# Sheet1.net
KiCad netlist of a schematic drawn in Altium Designer
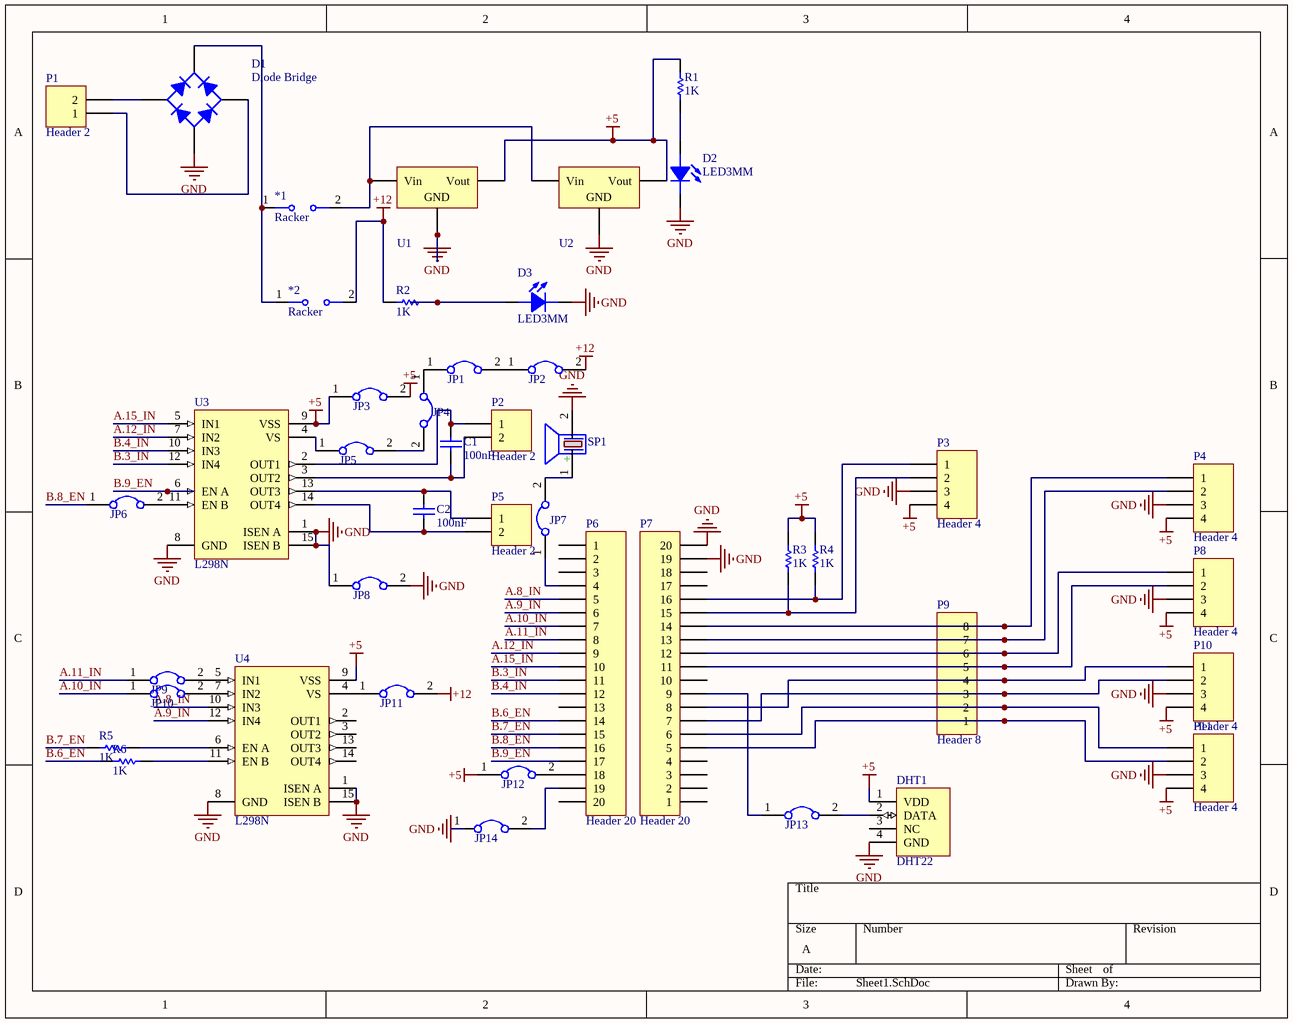
[diagram p0: Sheet1.SchDoc]

(export (version "E")
  (design (tool "Eeschema 10.0.6"))
  (components
    (comp (ref "*1") (value "Racker") (footprint "Racker 2 Pin") (libsource (lib "Switch") (part "Racker")))
    (comp (ref "*2") (value "Racker") (footprint "Racker 2 Pin") (libsource (lib "Switch") (part "Racker")))
    (comp (ref "C1")
      (value "100nF")
      (footprint "Cap-100nF")
      (description "CAP Ceramic Total")
      (fields (field (name "DESIGNER") "Ali Hafizi"))
      (libsource (lib "Altium") (part "CAP CERAMIC TOTAL SIZE"))
    )
    (comp (ref "C2")
      (value "100nF")
      (footprint "Cap-100nF")
      (description "CAP Ceramic Total")
      (fields (field (name "DESIGNER") "Ali Hafizi"))
      (libsource (lib "Altium") (part "CAP CERAMIC TOTAL SIZE"))
    )
    (comp (ref "D1")
      (value "Diode Bridge")
      (footprint "Bridge KBL PACKAGE")
      (description "Full Wave Diode Bridge")
      (fields (field (name "DESIGNER") "Abbas Basereh"))
      (libsource (lib "Altium") (part "Diode Bridge TOTAL SIZE"))
    )
    (comp (ref "D2")
      (value "LED3MM")
      (footprint "LED3mm_GRN")
      (description "Light Emitting Diode")
      (fields (field (name "DESIGNER") "Ali Hafizi"))
      (libsource (lib "Altium") (part "LED 3MM"))
    )
    (comp (ref "D3")
      (value "LED3MM")
      (footprint "LED3mm_GRN")
      (description "Light Emitting Diode")
      (fields (field (name "DESIGNER") "Ali Hafizi"))
      (libsource (lib "Altium") (part "LED 3MM"))
    )
    (comp (ref "DHT1")
      (value "DHT22")
      (footprint "DHT22")
      (description "Digital Humidity & Temprature Sensor")
      (libsource (lib "Altium") (part "DHT22"))
    )
    (comp (ref "JP1") (value "Jumper") (footprint "Jumper") (libsource (lib "Altium") (part "Jumper")))
    (comp (ref "JP2") (value "Jumper") (footprint "Jumper") (libsource (lib "Altium") (part "Jumper")))
    (comp (ref "JP3") (value "Jumper") (footprint "Jumper") (libsource (lib "Altium") (part "Jumper")))
    (comp (ref "JP4") (value "Jumper") (footprint "Jumper") (libsource (lib "Altium") (part "Jumper")))
    (comp (ref "JP5") (value "Jumper") (footprint "Jumper") (libsource (lib "Altium") (part "Jumper")))
    (comp (ref "JP6") (value "Jumper") (footprint "Jumper") (libsource (lib "Altium") (part "Jumper")))
    (comp (ref "JP7") (value "Jumper") (footprint "Jumper") (libsource (lib "Altium") (part "Jumper")))
    (comp (ref "JP8") (value "Jumper") (footprint "Jumper") (libsource (lib "Altium") (part "Jumper")))
    (comp (ref "JP9") (value "Jumper") (footprint "Jumper") (libsource (lib "Altium") (part "Jumper")))
    (comp (ref "JP10") (value "Jumper") (footprint "Jumper") (libsource (lib "Altium") (part "Jumper")))
    (comp (ref "JP11") (value "Jumper") (footprint "Jumper") (libsource (lib "Altium") (part "Jumper")))
    (comp (ref "JP12") (value "Jumper") (footprint "Jumper") (libsource (lib "Altium") (part "Jumper")))
    (comp (ref "JP13") (value "Jumper") (footprint "Jumper") (libsource (lib "Altium") (part "Jumper")))
    (comp (ref "JP14") (value "Jumper") (footprint "Jumper") (libsource (lib "Altium") (part "Jumper")))
    (comp (ref "P1")
      (value "Header 2")
      (footprint "HDR1X2")
      (description "Header, 2-Pin")
      (fields (field (name "PUBLISHER") "Altium Limited"))
      (libsource (lib "") (part "Header 2_1"))
    )
    (comp (ref "P2")
      (value "Header 2")
      (footprint "HDR1X2")
      (description "Header, 2-Pin")
      (fields (field (name "PUBLISHER") "Altium Limited"))
      (libsource (lib "Altium") (part "Header 2"))
    )
    (comp (ref "P3")
      (value "Header 4")
      (footprint "HDR1X4")
      (description "Header, 4-Pin")
      (fields (field (name "PUBLISHER") "Altium Limited"))
      (libsource (lib "Altium") (part "Header 4"))
    )
    (comp (ref "P4")
      (value "Header 4")
      (footprint "HDR1X4")
      (description "Header, 4-Pin")
      (fields (field (name "PUBLISHER") "Altium Limited"))
      (libsource (lib "Altium") (part "Header 4"))
    )
    (comp (ref "P5")
      (value "Header 2")
      (footprint "HDR1X2")
      (description "Header, 2-Pin")
      (fields (field (name "PUBLISHER") "Altium Limited"))
      (libsource (lib "Altium") (part "Header 2"))
    )
    (comp (ref "P6")
      (value "Header 20")
      (footprint "HDR1X20")
      (description "Header, 20-Pin")
      (fields (field (name "PUBLISHER") "Altium Limited"))
      (libsource (lib "") (part "Header 20_1"))
    )
    (comp (ref "P7")
      (value "Header 20")
      (footprint "HDR1X20")
      (description "Header, 20-Pin")
      (fields (field (name "PUBLISHER") "Altium Limited"))
      (libsource (lib "Altium") (part "Header 20"))
    )
    (comp (ref "P8")
      (value "Header 4")
      (footprint "HDR1X4")
      (description "Header, 4-Pin")
      (fields (field (name "PUBLISHER") "Altium Limited"))
      (libsource (lib "Altium") (part "Header 4"))
    )
    (comp (ref "P9")
      (value "Header 8")
      (footprint "HDR1X8")
      (description "Header, 8-Pin")
      (fields (field (name "PUBLISHER") "Altium Limited"))
      (libsource (lib "Altium") (part "Header 8"))
    )
    (comp (ref "P10")
      (value "Header 4")
      (footprint "HDR1X4")
      (description "Header, 4-Pin")
      (fields (field (name "PUBLISHER") "Altium Limited"))
      (libsource (lib "Altium") (part "Header 4"))
    )
    (comp (ref "P11")
      (value "Header 4")
      (footprint "HDR1X4")
      (description "Header, 4-Pin")
      (fields (field (name "PUBLISHER") "Altium Limited"))
      (libsource (lib "Altium") (part "Header 4"))
    )
    (comp (ref "R1")
      (value "1K")
      (footprint "RES-(1/4)")
      (description "TOTAL DIP RESISTOR PACK")
      (fields (field (name "DESIGNER") "Ali Hafizi"))
      (libsource (lib "Altium") (part "RES DIP PACKAGE"))
    )
    (comp (ref "R2")
      (value "1K")
      (footprint "RES-(1/4)")
      (description "TOTAL DIP RESISTOR PACK")
      (fields (field (name "DESIGNER") "Ali Hafizi"))
      (libsource (lib "Altium") (part "RES DIP PACKAGE"))
    )
    (comp (ref "R3")
      (value "1K")
      (footprint "RES-(1/4)")
      (description "TOTAL DIP RESISTOR PACK")
      (fields (field (name "DESIGNER") "Ali Hafizi"))
      (libsource (lib "Altium") (part "RES DIP PACKAGE"))
    )
    (comp (ref "R4")
      (value "1K")
      (footprint "RES-(1/4)")
      (description "TOTAL DIP RESISTOR PACK")
      (fields (field (name "DESIGNER") "Ali Hafizi"))
      (libsource (lib "Altium") (part "RES DIP PACKAGE"))
    )
    (comp (ref "R5")
      (value "1K")
      (footprint "RES-(1/4)")
      (description "TOTAL DIP RESISTOR PACK")
      (fields (field (name "DESIGNER") "Ali Hafizi"))
      (libsource (lib "Altium") (part "RES DIP PACKAGE"))
    )
    (comp (ref "R6")
      (value "1K")
      (footprint "RES-(1/4)")
      (description "TOTAL DIP RESISTOR PACK")
      (fields (field (name "DESIGNER") "Ali Hafizi"))
      (libsource (lib "Altium") (part "RES DIP PACKAGE"))
    )
    (comp (ref "SP1")
      (value "~")
      (footprint "BUZZER 7.62mm DC")
      (description "PIEZO BUZZER ACTIVE")
      (fields (field (name "DESIGNER") "Abbas Basereh") (field (name "PUBLISHER") "Abbas Basereh"))
      (libsource (lib "Altium") (part "PIEZO BUZZER"))
    )
    (comp (ref "U1")
      (value "L7805CV")
      (footprint "TO-220 AB")
      (description "Linear Voltage Regulator IC Positive FIXED")
      (fields (field (name "MANUFACTURER") "STMicroelectronics") (field (name "DESIGNER") "Abbas Basereh"))
      (libsource (lib "Altium") (part "L7805CV-Linear Voltage Regulator IC Positive 1 Output 5V 1.5A TO-220AB"))
    )
    (comp (ref "U2")
      (value "L7805CV")
      (footprint "TO-220 AB")
      (description "Linear Voltage Regulator IC Positive FIXED")
      (fields (field (name "MANUFACTURER") "STMicroelectronics") (field (name "DESIGNER") "Abbas Basereh"))
      (libsource (lib "Altium") (part "L7805CV-Linear Voltage Regulator IC Positive 1 Output 5V 1.5A TO-220AB"))
    )
    (comp (ref "U3")
      (value "L298N")
      (footprint "Multiwatt15V")
      (description "Dual Full Bridge Driver")
      (fields (field (name "PUBLISHER") "Altium Limited"))
      (libsource (lib "Altium") (part "L298N"))
    )
    (comp (ref "U4")
      (value "L298N")
      (footprint "Multiwatt15V")
      (description "Dual Full Bridge Driver")
      (fields (field (name "PUBLISHER") "Altium Limited"))
      (libsource (lib "Altium") (part "L298N"))
    )
  )
  (nets
    (net (code "1") (name "+5") (class "Default")
      (node (ref "DHT1") (pin "1") (pinfunction "VDD_1") (pintype "power_in"))
      (node (ref "JP12") (pin "1") (pinfunction "1_1") (pintype "passive"))
      (node (ref "JP3") (pin "1") (pinfunction "1_1") (pintype "passive"))
      (node (ref "JP3") (pin "2") (pinfunction "2_2") (pintype "passive"))
      (node (ref "P10") (pin "4") (pinfunction "4_4") (pintype "passive"))
      (node (ref "P11") (pin "4") (pinfunction "4_4") (pintype "passive"))
      (node (ref "P3") (pin "4") (pinfunction "4_4") (pintype "passive"))
      (node (ref "P4") (pin "4") (pinfunction "4_4") (pintype "passive"))
      (node (ref "P8") (pin "4") (pinfunction "4_4") (pintype "passive"))
      (node (ref "R1") (pin "2") (pinfunction "2_2") (pintype "passive"))
      (node (ref "R3") (pin "2") (pinfunction "2_2") (pintype "passive"))
      (node (ref "R4") (pin "2") (pinfunction "2_2") (pintype "passive"))
      (node (ref "U1") (pin "3") (pinfunction "Vout_3") (pintype "passive"))
      (node (ref "U2") (pin "3") (pinfunction "Vout_3") (pintype "passive"))
      (node (ref "U3") (pin "9") (pinfunction "VSS_9") (pintype "power_in"))
      (node (ref "U4") (pin "9") (pinfunction "VSS_9") (pintype "power_in"))
    )
    (net (code "2") (name "+12") (class "Default")
      (node (ref "*2") (pin "2") (pinfunction "2_2") (pintype "passive"))
      (node (ref "JP11") (pin "2") (pinfunction "2_2") (pintype "passive"))
      (node (ref "JP2") (pin "2") (pinfunction "2_2") (pintype "passive"))
      (node (ref "R2") (pin "2") (pinfunction "2_2") (pintype "passive"))
    )
    (net (code "3") (name "/A.8_IN") (class "Default")
      (node (ref "P6") (pin "5") (pinfunction "5_5") (pintype "passive"))
      (node (ref "U4") (pin "10") (pinfunction "IN3_10") (pintype "input"))
    )
    (net (code "4") (name "/A.9_IN") (class "Default")
      (node (ref "P6") (pin "6") (pinfunction "6_6") (pintype "passive"))
      (node (ref "U4") (pin "12") (pinfunction "IN4_12") (pintype "input"))
    )
    (net (code "5") (name "/A.10_IN") (class "Default")
      (node (ref "JP10") (pin "1") (pinfunction "1_1") (pintype "passive"))
      (node (ref "P6") (pin "7") (pinfunction "7_7") (pintype "passive"))
    )
    (net (code "6") (name "/A.11_IN") (class "Default")
      (node (ref "JP9") (pin "1") (pinfunction "1_1") (pintype "passive"))
      (node (ref "P6") (pin "8") (pinfunction "8_8") (pintype "passive"))
    )
    (net (code "7") (name "/A.12_IN") (class "Default")
      (node (ref "P6") (pin "9") (pinfunction "9_9") (pintype "passive"))
      (node (ref "U3") (pin "7") (pinfunction "IN2_7") (pintype "input"))
    )
    (net (code "8") (name "/A.15_IN") (class "Default")
      (node (ref "P6") (pin "10") (pinfunction "10_10") (pintype "passive"))
      (node (ref "U3") (pin "5") (pinfunction "IN1_5") (pintype "input"))
    )
    (net (code "9") (name "/B.3_IN") (class "Default")
      (node (ref "P6") (pin "11") (pinfunction "11_11") (pintype "passive"))
      (node (ref "U3") (pin "12") (pinfunction "IN4_12") (pintype "input"))
    )
    (net (code "10") (name "/B.4_IN") (class "Default")
      (node (ref "P6") (pin "12") (pinfunction "12_12") (pintype "passive"))
      (node (ref "U3") (pin "10") (pinfunction "IN3_10") (pintype "input"))
    )
    (net (code "11") (name "/B.6_EN") (class "Default")
      (node (ref "P6") (pin "14") (pinfunction "14_14") (pintype "passive"))
      (node (ref "R6") (pin "1") (pinfunction "1_1") (pintype "passive"))
    )
    (net (code "12") (name "/B.7_EN") (class "Default")
      (node (ref "P6") (pin "15") (pinfunction "15_15") (pintype "passive"))
      (node (ref "R5") (pin "1") (pinfunction "1_1") (pintype "passive"))
    )
    (net (code "13") (name "/B.8_EN") (class "Default")
      (node (ref "JP6") (pin "1") (pinfunction "1_1") (pintype "passive"))
      (node (ref "P6") (pin "16") (pinfunction "16_16") (pintype "passive"))
    )
    (net (code "14") (name "/B.9_EN") (class "Default")
      (node (ref "P6") (pin "17") (pinfunction "17_17") (pintype "passive"))
      (node (ref "U3") (pin "6") (pinfunction "EN_A_6") (pintype "input"))
    )
    (net (code "15") (name "GND") (class "Default")
      (node (ref "D1") (pin "4") (pinfunction "-_4") (pintype "passive"))
      (node (ref "D2") (pin "2") (pinfunction "CATHODE_2") (pintype "passive"))
      (node (ref "D3") (pin "2") (pinfunction "CATHODE_2") (pintype "passive"))
      (node (ref "DHT1") (pin "4") (pinfunction "GND_4") (pintype "power_in"))
      (node (ref "JP14") (pin "1") (pinfunction "1_1") (pintype "passive"))
      (node (ref "JP8") (pin "1") (pinfunction "1_1") (pintype "passive"))
      (node (ref "JP8") (pin "2") (pinfunction "2_2") (pintype "passive"))
      (node (ref "P10") (pin "3") (pinfunction "3_3") (pintype "passive"))
      (node (ref "P11") (pin "3") (pinfunction "3_3") (pintype "passive"))
      (node (ref "P3") (pin "3") (pinfunction "3_3") (pintype "passive"))
      (node (ref "P4") (pin "3") (pinfunction "3_3") (pintype "passive"))
      (node (ref "P7") (pin "19") (pinfunction "19_19") (pintype "passive"))
      (node (ref "P7") (pin "20") (pinfunction "20_20") (pintype "passive"))
      (node (ref "P8") (pin "3") (pinfunction "3_3") (pintype "passive"))
      (node (ref "SP1") (pin "2") (pinfunction "-_2") (pintype "passive"))
      (node (ref "U1") (pin "2") (pinfunction "GND_2") (pintype "passive"))
      (node (ref "U2") (pin "2") (pinfunction "GND_2") (pintype "passive"))
      (node (ref "U3") (pin "1") (pinfunction "ISEN_A_1") (pintype "passive"))
      (node (ref "U3") (pin "15") (pinfunction "ISEN_B_15") (pintype "passive"))
      (node (ref "U3") (pin "8") (pinfunction "GND_8") (pintype "power_in"))
      (node (ref "U4") (pin "1") (pinfunction "ISEN_A_1") (pintype "passive"))
      (node (ref "U4") (pin "15") (pinfunction "ISEN_B_15") (pintype "passive"))
      (node (ref "U4") (pin "8") (pinfunction "GND_8") (pintype "power_in"))
    )
    (net (code "16") (name "Net-(*1-Button)") (class "Default")
      (node (ref "*1") (pin "1") (pinfunction "Button_1") (pintype "passive"))
      (node (ref "*2") (pin "1") (pinfunction "Button_1") (pintype "passive"))
      (node (ref "D1") (pin "1") (pinfunction "+_1") (pintype "passive"))
    )
    (net (code "17") (name "Net-(D1-AC-Pad2)") (class "Default")
      (node (ref "D1") (pin "2") (pinfunction "AC_2") (pintype "passive"))
      (node (ref "P1") (pin "2") (pinfunction "2_2") (pintype "passive"))
    )
    (net (code "18") (name "Net-(D1-AC-Pad3)") (class "Default")
      (node (ref "D1") (pin "3") (pinfunction "AC_3") (pintype "passive"))
      (node (ref "P1") (pin "1") (pinfunction "1_1") (pintype "passive"))
    )
    (net (code "19") (name "Net-(D2-ANODE)") (class "Default")
      (node (ref "D2") (pin "1") (pinfunction "ANODE_1") (pintype "passive"))
      (node (ref "R1") (pin "1") (pinfunction "1_1") (pintype "passive"))
    )
    (net (code "20") (name "Net-(D3-ANODE)") (class "Default")
      (node (ref "D3") (pin "1") (pinfunction "ANODE_1") (pintype "passive"))
      (node (ref "R2") (pin "1") (pinfunction "1_1") (pintype "passive"))
    )
    (net (code "21") (name "Net-(DHT1-DATA)") (class "Default")
      (node (ref "DHT1") (pin "2") (pinfunction "DATA_2") (pintype "bidirectional"))
      (node (ref "JP13") (pin "2") (pinfunction "2_2") (pintype "passive"))
    )
    (net (code "22") (name "Net-(JP1-Pad1)") (class "Default")
      (node (ref "JP1") (pin "1") (pinfunction "1_1") (pintype "passive"))
      (node (ref "JP4") (pin "1") (pinfunction "1_1") (pintype "passive"))
    )
    (net (code "23") (name "Net-(JP1-Pad2)") (class "Default")
      (node (ref "JP1") (pin "2") (pinfunction "2_2") (pintype "passive"))
      (node (ref "JP2") (pin "1") (pinfunction "1_1") (pintype "passive"))
    )
    (net (code "24") (name "Net-(JP4-Pad2)") (class "Default")
      (node (ref "JP4") (pin "2") (pinfunction "2_2") (pintype "passive"))
      (node (ref "JP5") (pin "2") (pinfunction "2_2") (pintype "passive"))
    )
    (net (code "25") (name "Net-(JP7-Pad1)") (class "Default")
      (node (ref "JP7") (pin "1") (pinfunction "1_1") (pintype "passive"))
      (node (ref "P6") (pin "4") (pinfunction "4_4") (pintype "passive"))
    )
    (net (code "26") (name "Net-(JP12-Pad2)") (class "Default")
      (node (ref "JP12") (pin "2") (pinfunction "2_2") (pintype "passive"))
      (node (ref "P6") (pin "18") (pinfunction "18_18") (pintype "passive"))
    )
    (net (code "27") (name "Net-(JP13-Pad1)") (class "Default")
      (node (ref "JP13") (pin "1") (pinfunction "1_1") (pintype "passive"))
      (node (ref "P7") (pin "9") (pinfunction "9_9") (pintype "passive"))
    )
    (net (code "28") (name "Net-(JP14-Pad2)") (class "Default")
      (node (ref "JP14") (pin "2") (pinfunction "2_2") (pintype "passive"))
      (node (ref "P6") (pin "19") (pinfunction "19_19") (pintype "passive"))
    )
    (net (code "29") (name "Net-(P3-Pad1)") (class "Default")
      (node (ref "P3") (pin "1") (pinfunction "1_1") (pintype "passive"))
      (node (ref "P7") (pin "16") (pinfunction "16_16") (pintype "passive"))
      (node (ref "R4") (pin "1") (pinfunction "1_1") (pintype "passive"))
    )
    (net (code "30") (name "Net-(P3-Pad2)") (class "Default")
      (node (ref "P3") (pin "2") (pinfunction "2_2") (pintype "passive"))
      (node (ref "P7") (pin "15") (pinfunction "15_15") (pintype "passive"))
      (node (ref "R3") (pin "1") (pinfunction "1_1") (pintype "passive"))
    )
    (net (code "31") (name "Net-(P4-Pad1)") (class "Default")
      (node (ref "P4") (pin "1") (pinfunction "1_1") (pintype "passive"))
      (node (ref "P7") (pin "14") (pinfunction "14_14") (pintype "passive"))
      (node (ref "P9") (pin "8") (pinfunction "8_8") (pintype "passive"))
    )
    (net (code "32") (name "Net-(P4-Pad2)") (class "Default")
      (node (ref "P4") (pin "2") (pinfunction "2_2") (pintype "passive"))
      (node (ref "P7") (pin "13") (pinfunction "13_13") (pintype "passive"))
      (node (ref "P9") (pin "7") (pinfunction "7_7") (pintype "passive"))
    )
    (net (code "33") (name "Net-(P7-Pad11)") (class "Default")
      (node (ref "P7") (pin "11") (pinfunction "11_11") (pintype "passive"))
      (node (ref "P8") (pin "2") (pinfunction "2_2") (pintype "passive"))
      (node (ref "P9") (pin "5") (pinfunction "5_5") (pintype "passive"))
    )
    (net (code "34") (name "Net-(P7-Pad12)") (class "Default")
      (node (ref "P7") (pin "12") (pinfunction "12_12") (pintype "passive"))
      (node (ref "P8") (pin "1") (pinfunction "1_1") (pintype "passive"))
      (node (ref "P9") (pin "6") (pinfunction "6_6") (pintype "passive"))
    )
    (net (code "35") (name "Net-(P10-Pad1)") (class "Default")
      (node (ref "P10") (pin "1") (pinfunction "1_1") (pintype "passive"))
      (node (ref "P7") (pin "8") (pinfunction "8_8") (pintype "passive"))
      (node (ref "P9") (pin "4") (pinfunction "4_4") (pintype "passive"))
    )
    (net (code "36") (name "Net-(P10-Pad2)") (class "Default")
      (node (ref "P10") (pin "2") (pinfunction "2_2") (pintype "passive"))
      (node (ref "P7") (pin "7") (pinfunction "7_7") (pintype "passive"))
      (node (ref "P9") (pin "3") (pinfunction "3_3") (pintype "passive"))
    )
    (net (code "37") (name "Net-(P11-Pad1)") (class "Default")
      (node (ref "P11") (pin "1") (pinfunction "1_1") (pintype "passive"))
      (node (ref "P7") (pin "6") (pinfunction "6_6") (pintype "passive"))
      (node (ref "P9") (pin "2") (pinfunction "2_2") (pintype "passive"))
    )
    (net (code "38") (name "Net-(P11-Pad2)") (class "Default")
      (node (ref "P11") (pin "2") (pinfunction "2_2") (pintype "passive"))
      (node (ref "P7") (pin "5") (pinfunction "5_5") (pintype "passive"))
      (node (ref "P9") (pin "1") (pinfunction "1_1") (pintype "passive"))
    )
    (net (code "39") (name "Net-(SP1-+)") (class "Default")
      (node (ref "JP7") (pin "2") (pinfunction "2_2") (pintype "passive"))
      (node (ref "SP1") (pin "1") (pinfunction "+_1") (pintype "passive"))
    )
    (net (code "40") (name "Net-(U1-Vin)") (class "Default")
      (node (ref "*1") (pin "2") (pinfunction "2_2") (pintype "passive"))
      (node (ref "U1") (pin "1") (pinfunction "Vin_1") (pintype "passive"))
      (node (ref "U2") (pin "1") (pinfunction "Vin_1") (pintype "passive"))
    )
    (net (code "41") (name "Net-(U3-EN_B)") (class "Default")
      (node (ref "JP6") (pin "2") (pinfunction "2_2") (pintype "passive"))
      (node (ref "U3") (pin "11") (pinfunction "EN_B_11") (pintype "input"))
    )
    (net (code "42") (name "Net-(U3-OUT1)") (class "Default")
      (node (ref "C1") (pin "2") (pinfunction "2_2") (pintype "passive"))
      (node (ref "P2") (pin "1") (pinfunction "1_1") (pintype "passive"))
      (node (ref "U3") (pin "2") (pinfunction "OUT1_2") (pintype "output"))
    )
    (net (code "43") (name "Net-(U3-OUT2)") (class "Default")
      (node (ref "C1") (pin "1") (pinfunction "1_1") (pintype "passive"))
      (node (ref "P2") (pin "2") (pinfunction "2_2") (pintype "passive"))
      (node (ref "U3") (pin "3") (pinfunction "OUT2_3") (pintype "output"))
    )
    (net (code "44") (name "Net-(U3-OUT3)") (class "Default")
      (node (ref "C2") (pin "2") (pinfunction "2_2") (pintype "passive"))
      (node (ref "P5") (pin "1") (pinfunction "1_1") (pintype "passive"))
      (node (ref "U3") (pin "13") (pinfunction "OUT3_13") (pintype "output"))
    )
    (net (code "45") (name "Net-(U3-OUT4)") (class "Default")
      (node (ref "C2") (pin "1") (pinfunction "1_1") (pintype "passive"))
      (node (ref "P5") (pin "2") (pinfunction "2_2") (pintype "passive"))
      (node (ref "U3") (pin "14") (pinfunction "OUT4_14") (pintype "output"))
    )
    (net (code "46") (name "Net-(U3-VS)") (class "Default")
      (node (ref "JP5") (pin "1") (pinfunction "1_1") (pintype "passive"))
      (node (ref "U3") (pin "4") (pinfunction "VS_4") (pintype "power_in"))
    )
    (net (code "47") (name "Net-(U4-EN_A)") (class "Default")
      (node (ref "R5") (pin "2") (pinfunction "2_2") (pintype "passive"))
      (node (ref "U4") (pin "6") (pinfunction "EN_A_6") (pintype "input"))
    )
    (net (code "48") (name "Net-(U4-EN_B)") (class "Default")
      (node (ref "R6") (pin "2") (pinfunction "2_2") (pintype "passive"))
      (node (ref "U4") (pin "11") (pinfunction "EN_B_11") (pintype "input"))
    )
    (net (code "49") (name "Net-(U4-IN1)") (class "Default")
      (node (ref "JP9") (pin "2") (pinfunction "2_2") (pintype "passive"))
      (node (ref "U4") (pin "5") (pinfunction "IN1_5") (pintype "input"))
    )
    (net (code "50") (name "Net-(U4-IN2)") (class "Default")
      (node (ref "JP10") (pin "2") (pinfunction "2_2") (pintype "passive"))
      (node (ref "U4") (pin "7") (pinfunction "IN2_7") (pintype "input"))
    )
    (net (code "51") (name "Net-(U4-VS)") (class "Default")
      (node (ref "JP11") (pin "1") (pinfunction "1_1") (pintype "passive"))
      (node (ref "U4") (pin "4") (pinfunction "VS_4") (pintype "power_in"))
    )
    (net (code "52") (name "unconnected-(DHT1-NC-Pad3)") (class "Default")
      (node (ref "DHT1") (pin "3") (pinfunction "NC_3") (pintype "passive"))
    )
    (net (code "53") (name "unconnected-(P6-Pad1)") (class "Default")
      (node (ref "P6") (pin "1") (pinfunction "1_1") (pintype "passive"))
    )
    (net (code "54") (name "unconnected-(P6-Pad2)") (class "Default")
      (node (ref "P6") (pin "2") (pinfunction "2_2") (pintype "passive"))
    )
    (net (code "55") (name "unconnected-(P6-Pad3)") (class "Default")
      (node (ref "P6") (pin "3") (pinfunction "3_3") (pintype "passive"))
    )
    (net (code "56") (name "unconnected-(P6-Pad13)") (class "Default")
      (node (ref "P6") (pin "13") (pinfunction "13_13") (pintype "passive"))
    )
    (net (code "57") (name "unconnected-(P6-Pad20)") (class "Default")
      (node (ref "P6") (pin "20") (pinfunction "20_20") (pintype "passive"))
    )
    (net (code "58") (name "unconnected-(P7-Pad1)") (class "Default")
      (node (ref "P7") (pin "1") (pinfunction "1_1") (pintype "passive"))
    )
    (net (code "59") (name "unconnected-(P7-Pad2)") (class "Default")
      (node (ref "P7") (pin "2") (pinfunction "2_2") (pintype "passive"))
    )
    (net (code "60") (name "unconnected-(P7-Pad3)") (class "Default")
      (node (ref "P7") (pin "3") (pinfunction "3_3") (pintype "passive"))
    )
    (net (code "61") (name "unconnected-(P7-Pad4)") (class "Default")
      (node (ref "P7") (pin "4") (pinfunction "4_4") (pintype "passive"))
    )
    (net (code "62") (name "unconnected-(P7-Pad10)") (class "Default")
      (node (ref "P7") (pin "10") (pinfunction "10_10") (pintype "passive"))
    )
    (net (code "63") (name "unconnected-(P7-Pad17)") (class "Default")
      (node (ref "P7") (pin "17") (pinfunction "17_17") (pintype "passive"))
    )
    (net (code "64") (name "unconnected-(P7-Pad18)") (class "Default")
      (node (ref "P7") (pin "18") (pinfunction "18_18") (pintype "passive"))
    )
    (net (code "65") (name "unconnected-(U4-OUT1-Pad2)") (class "Default")
      (node (ref "U4") (pin "2") (pinfunction "OUT1_2") (pintype "output"))
    )
    (net (code "66") (name "unconnected-(U4-OUT2-Pad3)") (class "Default")
      (node (ref "U4") (pin "3") (pinfunction "OUT2_3") (pintype "output"))
    )
    (net (code "67") (name "unconnected-(U4-OUT3-Pad13)") (class "Default")
      (node (ref "U4") (pin "13") (pinfunction "OUT3_13") (pintype "output"))
    )
    (net (code "68") (name "unconnected-(U4-OUT4-Pad14)") (class "Default")
      (node (ref "U4") (pin "14") (pinfunction "OUT4_14") (pintype "output"))
    )
  )
)
